# D2_oldVersion.net
KiCad netlist of a schematic drawn in Altium Designer
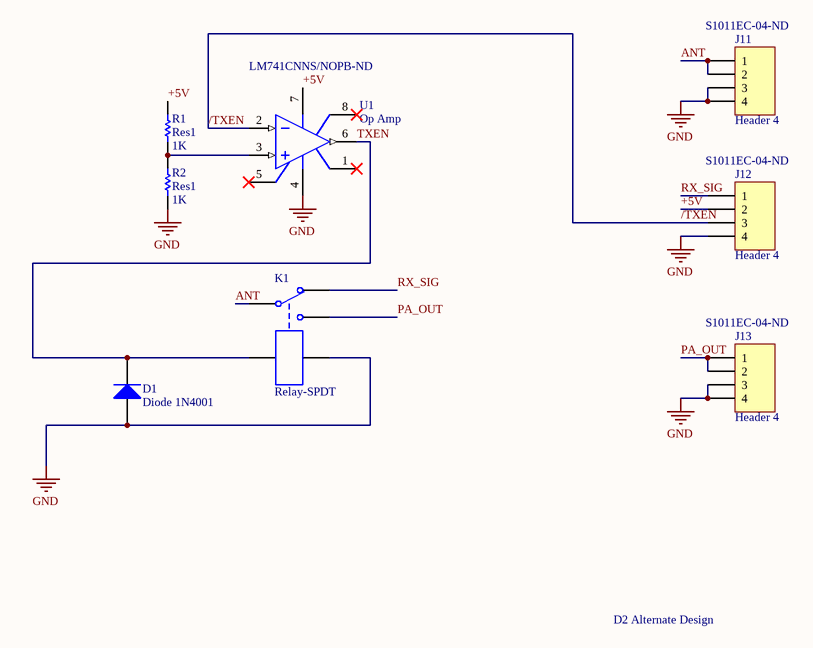
[diagram p0: D2_oldVersion.SchDoc]

(export (version "E")
  (design (tool "Eeschema 10.0.6"))
  (components
    (comp (ref "D1")
      (value "Diode 1N4001")
      (footprint "DO-41")
      (description "1 Amp General Purpose Rectifier")
      (fields (field (name "PUBLISHER") "Altium Limited"))
      (libsource (lib "Miscellaneous Devices") (part "Diode 1N4001"))
    )
    (comp (ref "J11")
      (value "Header 4")
      (footprint "HDR1X4")
      (description "Conn Header Vert 4POS 2.54MM")
      (fields
        (field (name "SUPPLIER PART NUMBER 1") "S1011EC-04-ND")
        (field (name "MANUFACTURER") "Sullins")
        (field (name "MANUFACTURER PART NUMBER") "PRPC004SAAN-RC")
        (field (name "PUBLISHER") "Altium Limited")
      )
      (libsource (lib "Miscellaneous Connectors") (part "Header 4"))
    )
    (comp (ref "J12")
      (value "Header 4")
      (footprint "HDR1X4")
      (description "Conn Header Vert 4POS 2.54MM")
      (fields
        (field (name "SUPPLIER PART NUMBER 1") "S1011EC-04-ND")
        (field (name "MANUFACTURER") "Sullins")
        (field (name "MANUFACTURER PART NUMBER") "PRPC004SAAN-RC")
        (field (name "PUBLISHER") "Altium Limited")
      )
      (libsource (lib "Miscellaneous Connectors") (part "Header 4"))
    )
    (comp (ref "J13")
      (value "Header 4")
      (footprint "HDR1X4")
      (description "Conn Header Vert 4POS 2.54MM")
      (fields
        (field (name "SUPPLIER PART NUMBER 1") "S1011EC-04-ND")
        (field (name "MANUFACTURER") "Sullins")
        (field (name "MANUFACTURER PART NUMBER") "PRPC004SAAN-RC")
        (field (name "PUBLISHER") "Altium Limited")
      )
      (libsource (lib "Miscellaneous Connectors") (part "Header 4"))
    )
    (comp (ref "K1")
      (value "Relay-SPDT")
      (footprint "MODULE5B")
      (description "Single-Pole Dual-Throw Relay")
      (fields (field (name "PUBLISHER") "Altium Limited"))
      (libsource (lib "Miscellaneous Devices") (part "Relay-SPDT"))
    )
    (comp (ref "R1")
      (value "Res1")
      (footprint "AXIAL-0.1-RES")
      (description "Resistor")
      (fields
        (field (name "MANUFACTURER PART NUMBER") "CFR-25JB-52-1K")
        (field (name "TOLERANCE") "0.05")
        (field (name "ALTIUM_VALUE") "1K")
        (field (name "PUBLISHER") "Altium Limited")
      )
      (libsource (lib "ECE295-Resistors-TH") (part "RES 1K OHM 5% 1/4W AXIAL"))
    )
    (comp (ref "R2")
      (value "Res1")
      (footprint "AXIAL-0.1-RES")
      (description "Resistor")
      (fields
        (field (name "MANUFACTURER PART NUMBER") "CFR-25JB-52-1K")
        (field (name "TOLERANCE") "0.05")
        (field (name "ALTIUM_VALUE") "1K")
        (field (name "PUBLISHER") "Altium Limited")
      )
      (libsource (lib "ECE295-Resistors-TH") (part "RES 1K OHM 5% 1/4W AXIAL"))
    )
    (comp (ref "U1")
      (value "Op Amp")
      (footprint "H-08A")
      (description "Single 44V 1MHz operational amplifier 8-PDIP 0 to 70")
      (fields
        (field (name "SUPPLIER PART NUMBER 1") "LM741CNNS/NOPB-ND")
        (field (name "MANUFACTURER") "TI National Semiconductor")
        (field (name "MANUFACTURER PART NUMBER") "LM741CN/NOPB")
        (field (name "PUBLISHER") "Altium Limited")
      )
      (libsource (lib "Miscellaneous Devices") (part "Op Amp"))
    )
  )
  (nets
    (net (code "1") (name "/+5V") (class "Default")
      (node (ref "J12") (pin "2") (pinfunction "2_2") (pintype "passive"))
      (node (ref "R1") (pin "2") (pinfunction "2_2") (pintype "passive"))
      (node (ref "U1") (pin "7") (pinfunction "V+_7") (pintype "power_in"))
    )
    (net (code "2") (name "/ANT") (class "Default")
      (node (ref "J11") (pin "1") (pinfunction "1_1") (pintype "passive"))
      (node (ref "J11") (pin "2") (pinfunction "2_2") (pintype "passive"))
      (node (ref "K1") (pin "1") (pinfunction "1_1") (pintype "passive"))
    )
    (net (code "3") (name "/PA_OUT") (class "Default")
      (node (ref "J13") (pin "1") (pinfunction "1_1") (pintype "passive"))
      (node (ref "J13") (pin "2") (pinfunction "2_2") (pintype "passive"))
      (node (ref "K1") (pin "3") (pinfunction "3_3") (pintype "passive"))
    )
    (net (code "4") (name "/RX_SIG") (class "Default")
      (node (ref "J12") (pin "1") (pinfunction "1_1") (pintype "passive"))
      (node (ref "K1") (pin "2") (pinfunction "2_2") (pintype "passive"))
    )
    (net (code "5") (name "/TXEN") (class "Default")
      (node (ref "D1") (pin "2") (pinfunction "K_2") (pintype "passive"))
      (node (ref "K1") (pin "4") (pinfunction "4_4") (pintype "passive"))
      (node (ref "U1") (pin "6") (pinfunction "OUT_6") (pintype "output"))
    )
    (net (code "6") (name "/{slash}TXEN") (class "Default")
      (node (ref "J12") (pin "3") (pinfunction "3_3") (pintype "passive"))
      (node (ref "U1") (pin "2") (pinfunction "IN-_2") (pintype "input"))
    )
    (net (code "7") (name "GND") (class "Default")
      (node (ref "D1") (pin "1") (pinfunction "A_1") (pintype "passive"))
      (node (ref "J11") (pin "3") (pinfunction "3_3") (pintype "passive"))
      (node (ref "J11") (pin "4") (pinfunction "4_4") (pintype "passive"))
      (node (ref "J12") (pin "4") (pinfunction "4_4") (pintype "passive"))
      (node (ref "J13") (pin "3") (pinfunction "3_3") (pintype "passive"))
      (node (ref "J13") (pin "4") (pinfunction "4_4") (pintype "passive"))
      (node (ref "K1") (pin "5") (pinfunction "5_5") (pintype "passive"))
      (node (ref "R2") (pin "1") (pinfunction "1_1") (pintype "passive"))
      (node (ref "U1") (pin "4") (pinfunction "V-_4") (pintype "power_in"))
    )
    (net (code "8") (name "Net-(U1-IN+)") (class "Default")
      (node (ref "R1") (pin "1") (pinfunction "1_1") (pintype "passive"))
      (node (ref "R2") (pin "2") (pinfunction "2_2") (pintype "passive"))
      (node (ref "U1") (pin "3") (pinfunction "IN+_3") (pintype "input"))
    )
    (net (code "9") (name "unconnected-(U1-OS_NUL-Pad1)") (class "Default")
      (node (ref "U1") (pin "1") (pinfunction "OS_NUL_1") (pintype "passive+no_connect"))
    )
    (net (code "10") (name "unconnected-(U1-OS_NUL-Pad5)") (class "Default")
      (node (ref "U1") (pin "5") (pinfunction "OS_NUL_5") (pintype "passive+no_connect"))
    )
    (net (code "11") (name "unconnected-(U1-TAB-Pad8)") (class "Default")
      (node (ref "U1") (pin "8") (pinfunction "TAB_8") (pintype "passive+no_connect"))
    )
  )
)
